# Tone_Cushion.net
KiCad netlist of a schematic drawn in Altium Designer
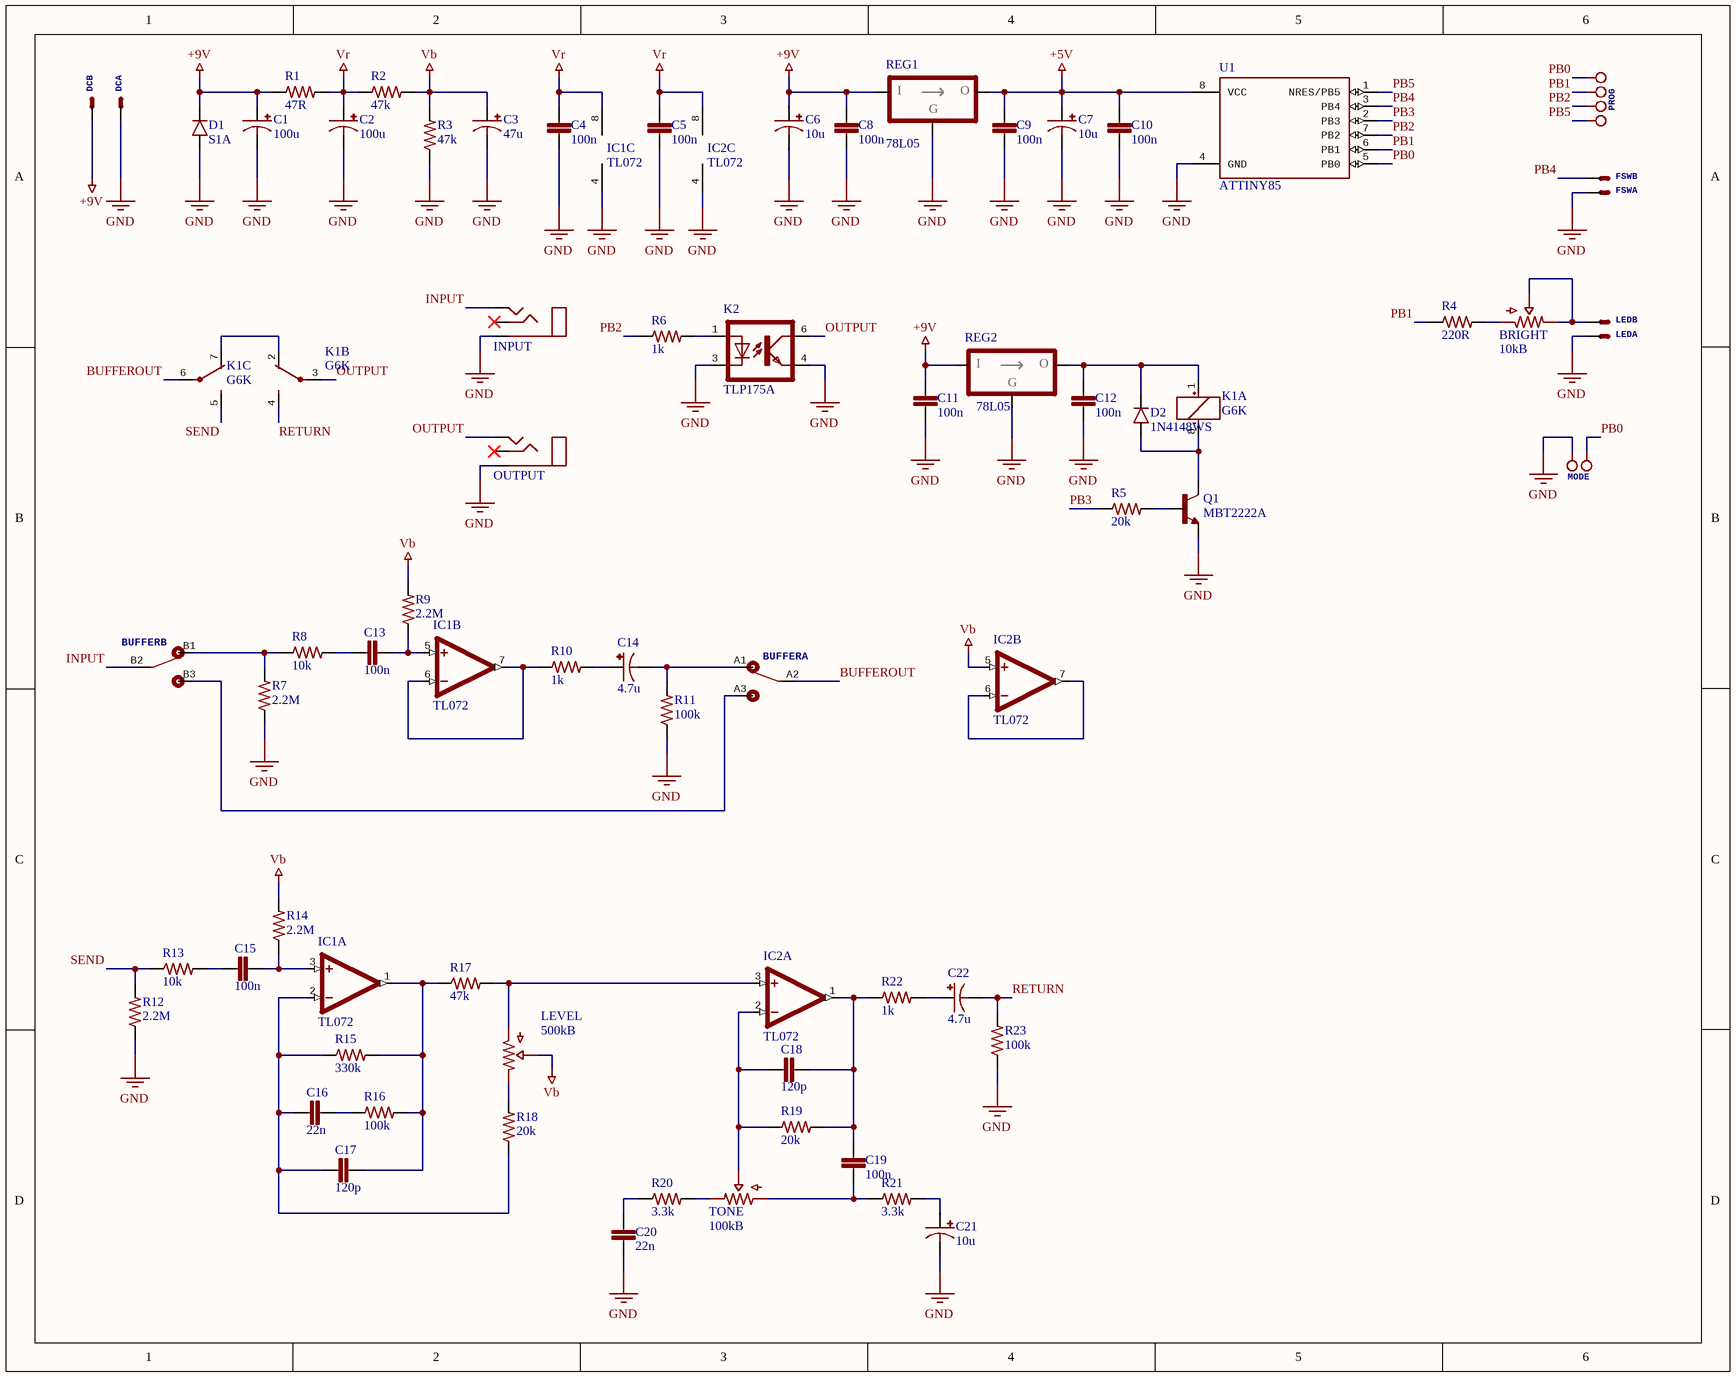
[diagram p0: Tone Cushion.SchDoc]

(export (version "E")
  (design (tool "Eeschema 10.0.6"))
  (components
    (comp (ref "BRIGHT")
      (value "10kB")
      (footprint "BOURNS_3362P")
      (description "10k Lin 3362P trimmer")
      (libsource (lib "Pedals") (part "TRIM_10kB_3362P"))
    )
    (comp (ref "BUFFER")
      (value "DPDT")
      (footprint "DPDT_SLIDE")
      (description "DPDT slide switch ON/ON")
      (libsource (lib "") (part "SW_SLIDE_DPDT_ON-ON_1"))
    )
    (comp (ref "C1")
      (value "100u")
      (footprint "CAPAE_D")
      (description "CAP ALUM 100UF 25V SMD")
      (fields
        (field (name "MANUFACTURER") "Multicomp")
        (field (name "MANUFACTURER PART NUMBER") "MCVVT025M101EA6L")
      )
      (libsource (lib "Pedals SMD") (part "MCVVT025M101EA6L"))
    )
    (comp (ref "C2")
      (value "100u")
      (footprint "CAPAE_D")
      (description "CAP ALUM 100UF 25V SMD")
      (fields
        (field (name "MANUFACTURER") "Multicomp")
        (field (name "MANUFACTURER PART NUMBER") "MCVVT025M101EA6L")
      )
      (libsource (lib "Pedals SMD") (part "MCVVT025M101EA6L"))
    )
    (comp (ref "C3")
      (value "47u")
      (footprint "CAPAE_D")
      (description "CAP ALUM 47UF 25V SMD")
      (fields
        (field (name "MANUFACTURER") "Multicomp")
        (field (name "MANUFACTURER PART NUMBER") "MCVVT025M470EA1L")
      )
      (libsource (lib "Pedals SMD") (part "MCVVT025M470EA1L"))
    )
    (comp (ref "C4")
      (value "100n")
      (footprint "CHIP_0603")
      (description "CAP CER 100NF 50V X7R 0603")
      (fields
        (field (name "MANUFACTURER") "Multicomp")
        (field (name "MANUFACTURER PART NUMBER") "MC0603B104K500CT")
      )
      (libsource (lib "Pedals SMD") (part "MC0603B104K500CT"))
    )
    (comp (ref "C5")
      (value "100n")
      (footprint "CHIP_0603")
      (description "CAP CER 100NF 50V X7R 0603")
      (fields
        (field (name "MANUFACTURER") "Multicomp")
        (field (name "MANUFACTURER PART NUMBER") "MC0603B104K500CT")
      )
      (libsource (lib "Pedals SMD") (part "MC0603B104K500CT"))
    )
    (comp (ref "C6")
      (value "10u")
      (footprint "CAPAE_B")
      (description "CAP ALUM 10UF 25V SMD")
      (fields
        (field (name "MANUFACTURER") "Multicomp")
        (field (name "MANUFACTURER PART NUMBER") "MCVVT025M100CA1L")
      )
      (libsource (lib "Pedals SMD") (part "MCVVT025M100CA1L"))
    )
    (comp (ref "C7")
      (value "10u")
      (footprint "CAPAE_B")
      (description "CAP ALUM 10UF 25V SMD")
      (fields
        (field (name "MANUFACTURER") "Multicomp")
        (field (name "MANUFACTURER PART NUMBER") "MCVVT025M100CA1L")
      )
      (libsource (lib "Pedals SMD") (part "MCVVT025M100CA1L"))
    )
    (comp (ref "C8")
      (value "100n")
      (footprint "CHIP_0603")
      (description "CAP CER 100NF 50V X7R 0603")
      (fields
        (field (name "MANUFACTURER") "Multicomp")
        (field (name "MANUFACTURER PART NUMBER") "MC0603B104K500CT")
      )
      (libsource (lib "Pedals SMD") (part "MC0603B104K500CT"))
    )
    (comp (ref "C9")
      (value "100n")
      (footprint "CHIP_0603")
      (description "CAP CER 100NF 50V X7R 0603")
      (fields
        (field (name "MANUFACTURER") "Multicomp")
        (field (name "MANUFACTURER PART NUMBER") "MC0603B104K500CT")
      )
      (libsource (lib "Pedals SMD") (part "MC0603B104K500CT"))
    )
    (comp (ref "C10")
      (value "100n")
      (footprint "CHIP_0603")
      (description "CAP CER 100NF 50V X7R 0603")
      (fields
        (field (name "MANUFACTURER") "Multicomp")
        (field (name "MANUFACTURER PART NUMBER") "MC0603B104K500CT")
      )
      (libsource (lib "Pedals SMD") (part "MC0603B104K500CT"))
    )
    (comp (ref "C11")
      (value "100n")
      (footprint "CHIP_0603")
      (description "CAP CER 100NF 50V X7R 0603")
      (fields
        (field (name "MANUFACTURER") "Multicomp")
        (field (name "MANUFACTURER PART NUMBER") "MC0603B104K500CT")
      )
      (libsource (lib "Pedals SMD") (part "MC0603B104K500CT"))
    )
    (comp (ref "C12")
      (value "100n")
      (footprint "CHIP_0603")
      (description "CAP CER 100NF 50V X7R 0603")
      (fields
        (field (name "MANUFACTURER") "Multicomp")
        (field (name "MANUFACTURER PART NUMBER") "MC0603B104K500CT")
      )
      (libsource (lib "Pedals SMD") (part "MC0603B104K500CT"))
    )
    (comp (ref "C13")
      (value "100n")
      (footprint "CHIP_1206")
      (description "CAP CER 100NF 50V C0G/NP0 1206")
      (fields
        (field (name "MANUFACTURER") "Murata")
        (field (name "MANUFACTURER PART NUMBER") "GRM31C5C1H104JA01L")
      )
      (libsource (lib "Pedals SMD") (part "GRM31C5C1H104JA01L"))
    )
    (comp (ref "C14")
      (value "4.7u")
      (footprint "CAPAE_C")
      (description "CAP ALUM 4.7UF 50V LESR SMD")
      (fields
        (field (name "MANUFACTURER") "Panasonic")
        (field (name "MANUFACTURER PART NUMBER") "EEEFC1H4R7R")
      )
      (libsource (lib "Pedals SMD") (part "EEEFC1H4R7R"))
    )
    (comp (ref "C15")
      (value "100n")
      (footprint "CHIP_1206")
      (description "CAP CER 100NF 50V C0G/NP0 1206")
      (fields
        (field (name "MANUFACTURER") "Murata")
        (field (name "MANUFACTURER PART NUMBER") "GRM31C5C1H104JA01L")
      )
      (libsource (lib "Pedals SMD") (part "GRM31C5C1H104JA01L"))
    )
    (comp (ref "C16")
      (value "22n")
      (footprint "CHIP_0805")
      (description "CAP CER 22NF 50V C0G/NP0 0805")
      (fields
        (field (name "MANUFACTURER") "Murata")
        (field (name "MANUFACTURER PART NUMBER") "GRM21B5C1H223JA01L")
      )
      (libsource (lib "") (part "GRM21B5C1H223JA01L_1"))
    )
    (comp (ref "C17")
      (value "120p")
      (footprint "CHIP_0603")
      (description "CAP CER 120PF 50V C0G/NP0 0603")
      (fields
        (field (name "MANUFACTURER") "Multicomp")
        (field (name "MANUFACTURER PART NUMBER") "MC0603N121J500CT")
      )
      (libsource (lib "Pedals SMD") (part "MC0603N121J500CT"))
    )
    (comp (ref "C18")
      (value "120p")
      (footprint "CHIP_0603")
      (description "CAP CER 120PF 50V C0G/NP0 0603")
      (fields
        (field (name "MANUFACTURER") "Multicomp")
        (field (name "MANUFACTURER PART NUMBER") "MC0603N121J500CT")
      )
      (libsource (lib "Pedals SMD") (part "MC0603N121J500CT"))
    )
    (comp (ref "C19")
      (value "100n")
      (footprint "CHIP_1206")
      (description "CAP CER 100NF 50V C0G/NP0 1206")
      (fields
        (field (name "MANUFACTURER") "Murata")
        (field (name "MANUFACTURER PART NUMBER") "GRM31C5C1H104JA01L")
      )
      (libsource (lib "") (part "GRM31C5C1H104JA01L_1"))
    )
    (comp (ref "C20")
      (value "22n")
      (footprint "CHIP_0805")
      (description "CAP CER 22NF 50V C0G/NP0 0805")
      (fields
        (field (name "MANUFACTURER") "Murata")
        (field (name "MANUFACTURER PART NUMBER") "GRM21B5C1H223JA01L")
      )
      (libsource (lib "Pedals SMD") (part "GRM21B5C1H223JA01L"))
    )
    (comp (ref "C21")
      (value "10u")
      (footprint "CAPAE_C")
      (description "CAP ALUM 10UF 20% 50V LESR SMD")
      (fields
        (field (name "MANUFACTURER") "Panasonic")
        (field (name "MANUFACTURER PART NUMBER") "EEEFC1H100P")
      )
      (libsource (lib "Pedals SMD") (part "EEEFC1H100P"))
    )
    (comp (ref "C22")
      (value "4.7u")
      (footprint "CAPAE_C")
      (description "CAP ALUM 4.7UF 50V LESR SMD")
      (fields
        (field (name "MANUFACTURER") "Panasonic")
        (field (name "MANUFACTURER PART NUMBER") "EEEFC1H4R7R")
      )
      (libsource (lib "Pedals SMD") (part "EEEFC1H4R7R"))
    )
    (comp (ref "D1")
      (value "S1A")
      (footprint "DO214")
      (description "DIODE GEN PURP 50V 1A SMA")
      (fields (field (name "MANUFACTURER") "ON Semiconductor / Fairchild"))
      (libsource (lib "Pedals SMD") (part "S1A"))
    )
    (comp (ref "D2")
      (value "1N4148WS")
      (footprint "SOD323")
      (description "DIODE GEN PURP 75V 150MA SOD323F")
      (fields (field (name "MANUFACTURER") "ON Semiconductor / Fairchild"))
      (libsource (lib "Pedals SMD") (part "1N4148WS"))
    )
    (comp (ref "DC")
      (value "J_JST-XH-02")
      (footprint "JST-XH-02")
      (description "2 Pins male XH header")
      (libsource (lib "Pedals") (part "J_JST-XH-02"))
    )
    (comp (ref "FSW")
      (value "J_JST-XH-02")
      (footprint "JST-XH-02")
      (description "2 Pins male XH header")
      (libsource (lib "Pedals") (part "J_JST-XH-02"))
    )
    (comp (ref "IC1")
      (value "TL072")
      (footprint "SO-8")
      (description "IC OPAMP JFET 4MHZ 8SO")
      (fields
        (field (name "MANUFACTURER") "STMicroelectronics")
        (field (name "MANUFACTURER PART NUMBER") "TL072CDT")
      )
      (libsource (lib "Pedals SMD") (part "TL072CDT"))
    )
    (comp (ref "IC2")
      (value "TL072")
      (footprint "SO-8")
      (description "IC OPAMP JFET 4MHZ 8SO")
      (fields
        (field (name "MANUFACTURER") "STMicroelectronics")
        (field (name "MANUFACTURER PART NUMBER") "TL072CDT")
      )
      (libsource (lib "Pedals SMD") (part "TL072CDT"))
    )
    (comp (ref "INPUT")
      (value "J_STEREO")
      (footprint "STEREO")
      (description "6.35mm stereo insulated socket jack PCB mounted")
      (libsource (lib "Pedals") (part "J_STEREO"))
    )
    (comp (ref "K1")
      (value "G6K")
      (footprint "G6K")
      (description "OMRON - G6K-2F 5DC - RELAY, SIGNAL, DPDT, 30VDC, 1A")
      (fields (field (name "MANUFACTURER") "Cliff") (field (name "MANUFACTURER PART NUMBER") "G6K-2F5DC"))
      (libsource (lib "") (part "G6K-2F5DC_2"))
    )
    (comp (ref "K2")
      (value "TLP175A")
      (footprint "TLP175A")
      (description "Toshiba TLP175A AC Input MOSFET Output Optocoupler, Surface Mount, 4-Pin SOIC")
      (fields (field (name "MANUFACTURER") "Toshiba"))
      (libsource (lib "Pedals SMD") (part "TLP175A"))
    )
    (comp (ref "LED")
      (value "J_JST-XH-02")
      (footprint "JST-XH-02")
      (description "2 Pins male XH header")
      (libsource (lib "Pedals") (part "J_JST-XH-02"))
    )
    (comp (ref "LEVEL")
      (value "500kB")
      (footprint "ALPHA_16mm_BOTTOM")
      (description "500k Lin potentiometer round shaft")
      (libsource (lib "Pedals") (part "POT_500kB_ALPHA_16mm"))
    )
    (comp (ref "MODE")
      (value "J_HEADER_2PINS")
      (footprint "HEADER_2PINS")
      (description "2 Pins male header")
      (libsource (lib "Pedals") (part "J_HEADER_2PINS"))
    )
    (comp (ref "OUTPUT")
      (value "J_STEREO")
      (footprint "STEREO")
      (description "6.35mm stereo insulated socket jack PCB mounted")
      (libsource (lib "Pedals") (part "J_STEREO"))
    )
    (comp (ref "PROG")
      (value "J_HEADER_4PINS_FEM")
      (footprint "HEADER_4Pins_FEM")
      (description "4 Pins female header")
      (libsource (lib "Pedals") (part "J_HEADER_4PINS_FEM"))
    )
    (comp (ref "Q1")
      (value "MBT2222A")
      (footprint "SOT323")
      (description "TRANS NPN 40V 0.6A SOT323")
      (fields
        (field (name "MANUFACTURER") "ON Semiconductor")
        (field (name "MANUFACTURER PART NUMBER") "MMBT2222AWT1G")
      )
      (libsource (lib "Pedals SMD") (part "MMBT2222AWT1G"))
    )
    (comp (ref "R1")
      (value "47R")
      (footprint "CHIP_R_1206")
      (description "RES SMD 47 OHM 1% 1/4W 1206")
      (fields
        (field (name "MANUFACTURER") "Vishay")
        (field (name "MANUFACTURER PART NUMBER") "CRCW120647R0FKEA")
      )
      (libsource (lib "Pedals SMD") (part "CRCW120647R0FKEA"))
    )
    (comp (ref "R2")
      (value "47k")
      (footprint "CHIP_R_1206")
      (description "RES SMD 47K OHM 1% 1/4W 1206")
      (fields
        (field (name "MANUFACTURER") "Vishay")
        (field (name "MANUFACTURER PART NUMBER") "CRCW120647K0FKEA")
      )
      (libsource (lib "Pedals SMD") (part "CRCW120647K0FKEA"))
    )
    (comp (ref "R3")
      (value "47k")
      (footprint "CHIP_R_1206")
      (description "RES SMD 47K OHM 1% 1/4W 1206")
      (fields
        (field (name "MANUFACTURER") "Vishay")
        (field (name "MANUFACTURER PART NUMBER") "CRCW120647K0FKEA")
      )
      (libsource (lib "Pedals SMD") (part "CRCW120647K0FKEA"))
    )
    (comp (ref "R4")
      (value "220R")
      (footprint "CHIP_R_1206")
      (description "RES SMD 220 OHM 1% 1/4W 1206")
      (fields
        (field (name "MANUFACTURER") "Vishay")
        (field (name "MANUFACTURER PART NUMBER") "CRCW1206220RFKEA")
      )
      (libsource (lib "Pedals SMD") (part "CRCW1206220RFKEA"))
    )
    (comp (ref "R5")
      (value "20k")
      (footprint "CHIP_R_0603")
      (description "RES SMD 20K OHM 1% 1/10W 0603")
      (fields
        (field (name "MANUFACTURER") "Vishay")
        (field (name "MANUFACTURER PART NUMBER") "CRCW060320K0FKEA")
      )
      (libsource (lib "Pedals SMD") (part "CRCW060320K0FKEA"))
    )
    (comp (ref "R6")
      (value "1k")
      (footprint "CHIP_R_0603")
      (description "RES SMD 1K OHM 1% 1/10W 0603")
      (fields
        (field (name "MANUFACTURER") "Vishay Dale")
        (field (name "MANUFACTURER PART NUMBER") "CRCW06031K00FKEA")
      )
      (libsource (lib "Pedals SMD") (part "CRCW06031K00FKEA"))
    )
    (comp (ref "R7")
      (value "2.2M")
      (footprint "CHIP_R_0603")
      (description "RES SMD 2.2M OHM 1% 1/10W 0603")
      (fields
        (field (name "MANUFACTURER") "Vishay")
        (field (name "MANUFACTURER PART NUMBER") "CRCW06032M20FKEA")
      )
      (libsource (lib "Pedals SMD") (part "CRCW06032M20FKEA"))
    )
    (comp (ref "R8")
      (value "10k")
      (footprint "CHIP_R_0603")
      (description "RES SMD 10K OHM 1% 1/10W 0603")
      (fields
        (field (name "MANUFACTURER") "Vishay")
        (field (name "MANUFACTURER PART NUMBER") "CRCW060310K0FKEA")
      )
      (libsource (lib "Pedals SMD") (part "CRCW060310K0FKEA"))
    )
    (comp (ref "R9")
      (value "2.2M")
      (footprint "CHIP_R_0603")
      (description "RES SMD 2.2M OHM 1% 1/10W 0603")
      (fields
        (field (name "MANUFACTURER") "Vishay")
        (field (name "MANUFACTURER PART NUMBER") "CRCW06032M20FKEA")
      )
      (libsource (lib "Pedals SMD") (part "CRCW06032M20FKEA"))
    )
    (comp (ref "R10")
      (value "1k")
      (footprint "CHIP_R_0603")
      (description "RES SMD 1K OHM 1% 1/10W 0603")
      (fields
        (field (name "MANUFACTURER") "Vishay Dale")
        (field (name "MANUFACTURER PART NUMBER") "CRCW06031K00FKEA")
      )
      (libsource (lib "Pedals SMD") (part "CRCW06031K00FKEA"))
    )
    (comp (ref "R11")
      (value "100k")
      (footprint "CHIP_R_0603")
      (description "RES SMD 100K OHM 1% 1/10W 0603")
      (fields
        (field (name "MANUFACTURER") "Vishay")
        (field (name "MANUFACTURER PART NUMBER") "CRCW0603100KFKEA")
      )
      (libsource (lib "Pedals SMD") (part "CRCW0603100KFKEA"))
    )
    (comp (ref "R12")
      (value "2.2M")
      (footprint "CHIP_R_0603")
      (description "RES SMD 2.2M OHM 1% 1/10W 0603")
      (fields
        (field (name "MANUFACTURER") "Vishay")
        (field (name "MANUFACTURER PART NUMBER") "CRCW06032M20FKEA")
      )
      (libsource (lib "Pedals SMD") (part "CRCW06032M20FKEA"))
    )
    (comp (ref "R13")
      (value "10k")
      (footprint "CHIP_R_0603")
      (description "RES SMD 10K OHM 1% 1/10W 0603")
      (fields
        (field (name "MANUFACTURER") "Vishay")
        (field (name "MANUFACTURER PART NUMBER") "CRCW060310K0FKEA")
      )
      (libsource (lib "Pedals SMD") (part "CRCW060310K0FKEA"))
    )
    (comp (ref "R14")
      (value "2.2M")
      (footprint "CHIP_R_0603")
      (description "RES SMD 2.2M OHM 1% 1/10W 0603")
      (fields
        (field (name "MANUFACTURER") "Vishay")
        (field (name "MANUFACTURER PART NUMBER") "CRCW06032M20FKEA")
      )
      (libsource (lib "Pedals SMD") (part "CRCW06032M20FKEA"))
    )
    (comp (ref "R15")
      (value "330k")
      (footprint "CHIP_R_0603")
      (description "RES SMD 330K OHM 1% 1/10W 0603")
      (fields
        (field (name "MANUFACTURER") "Vishay")
        (field (name "MANUFACTURER PART NUMBER") "CRCW0603330KFKEA")
      )
      (libsource (lib "Pedals SMD") (part "CRCW0603330KFKEA"))
    )
    (comp (ref "R16")
      (value "100k")
      (footprint "CHIP_R_0603")
      (description "RES SMD 100K OHM 1% 1/10W 0603")
      (fields
        (field (name "MANUFACTURER") "Vishay")
        (field (name "MANUFACTURER PART NUMBER") "CRCW0603100KFKEA")
      )
      (libsource (lib "Pedals SMD") (part "CRCW0603100KFKEA"))
    )
    (comp (ref "R17")
      (value "47k")
      (footprint "CHIP_R_0603")
      (description "RES SMD 47K OHM 1% 1/10W 0603")
      (fields
        (field (name "MANUFACTURER") "Vishay")
        (field (name "MANUFACTURER PART NUMBER") "CRCW060347K0FKEA")
      )
      (libsource (lib "Pedals SMD") (part "CRCW060347K0FKEA"))
    )
    (comp (ref "R18")
      (value "20k")
      (footprint "CHIP_R_0603")
      (description "RES SMD 20K OHM 1% 1/10W 0603")
      (fields
        (field (name "MANUFACTURER") "Vishay")
        (field (name "MANUFACTURER PART NUMBER") "CRCW060320K0FKEA")
      )
      (libsource (lib "Pedals SMD") (part "CRCW060320K0FKEA"))
    )
    (comp (ref "R19")
      (value "20k")
      (footprint "CHIP_R_0603")
      (description "RES SMD 20K OHM 1% 1/10W 0603")
      (fields
        (field (name "MANUFACTURER") "Vishay")
        (field (name "MANUFACTURER PART NUMBER") "CRCW060320K0FKEA")
      )
      (libsource (lib "Pedals SMD") (part "CRCW060320K0FKEA"))
    )
    (comp (ref "R20")
      (value "3.3k")
      (footprint "CHIP_R_0603")
      (description "RES SMD 3.3K OHM 1% 1/10W 0603")
      (fields
        (field (name "MANUFACTURER") "Vishay")
        (field (name "MANUFACTURER PART NUMBER") "CRCW06033K30FKEA")
      )
      (libsource (lib "Pedals SMD") (part "CRCW06033K30FKEA"))
    )
    (comp (ref "R21")
      (value "3.3k")
      (footprint "CHIP_R_0603")
      (description "RES SMD 3.3K OHM 1% 1/10W 0603")
      (fields
        (field (name "MANUFACTURER") "Vishay")
        (field (name "MANUFACTURER PART NUMBER") "CRCW06033K30FKEA")
      )
      (libsource (lib "Pedals SMD") (part "CRCW06033K30FKEA"))
    )
    (comp (ref "R22")
      (value "1k")
      (footprint "CHIP_R_0603")
      (description "RES SMD 1K OHM 1% 1/10W 0603")
      (fields
        (field (name "MANUFACTURER") "Vishay Dale")
        (field (name "MANUFACTURER PART NUMBER") "CRCW06031K00FKEA")
      )
      (libsource (lib "Pedals SMD") (part "CRCW06031K00FKEA"))
    )
    (comp (ref "R23")
      (value "100k")
      (footprint "CHIP_R_0603")
      (description "RES SMD 100K OHM 1% 1/10W 0603")
      (fields
        (field (name "MANUFACTURER") "Vishay")
        (field (name "MANUFACTURER PART NUMBER") "CRCW0603100KFKEA")
      )
      (libsource (lib "Pedals SMD") (part "CRCW0603100KFKEA"))
    )
    (comp (ref "REG1")
      (value "78L05")
      (footprint "SOT23-3")
      (description "TAIWAN SEMICONDUCTOR - TS78L05CX RFG - REG 3-TERMINAL 100MA, SMD, SOT23-3")
      (fields
        (field (name "MANUFACTURER") "Taiwan Semiconductor")
        (field (name "MANUFACTURER PART NUMBER") "TS78L05CXRFG")
      )
      (libsource (lib "Pedals SMD") (part "TS78L05CXRFG"))
    )
    (comp (ref "REG2")
      (value "78L05")
      (footprint "SOT23-3")
      (description "TAIWAN SEMICONDUCTOR - TS78L05CX RFG - REG 3-TERMINAL 100MA, SMD, SOT23-3")
      (fields
        (field (name "MANUFACTURER") "Taiwan Semiconductor")
        (field (name "MANUFACTURER PART NUMBER") "TS78L05CXRFG")
      )
      (libsource (lib "Pedals SMD") (part "TS78L05CXRFG"))
    )
    (comp (ref "TONE")
      (value "100kB")
      (footprint "ALPHA_16mm_BOTTOM")
      (description "100k Lin potentiometer round shaft")
      (libsource (lib "Pedals") (part "POT_100kB_ALPHA_16mm"))
    )
    (comp (ref "U1")
      (value "ATTINY85")
      (footprint "SOP8")
      (description "IC, 8BIT MCU, AVR TINY, 20MHZ, 8-SOIC")
      (fields
        (field (name "MANUFACTURER") "Microchip / Atmel")
        (field (name "MANUFACTURER PART NUMBER") "ATTINY85-20SU")
      )
      (libsource (lib "Pedals SMD") (part "ATTINY85-20SU"))
    )
  )
  (nets
    (net (code "1") (name "+5V") (class "Default")
      (node (ref "C10") (pin "1") (pinfunction "1_1") (pintype "passive"))
      (node (ref "C7") (pin "+") (pinfunction "+_+") (pintype "passive"))
      (node (ref "C9") (pin "1") (pinfunction "1_1") (pintype "passive"))
      (node (ref "REG1") (pin "1") (pinfunction "OUTPUT_1") (pintype "power_in"))
      (node (ref "U1") (pin "8") (pinfunction "VCC_8") (pintype "power_in"))
    )
    (net (code "2") (name "+9V") (class "Default")
      (node (ref "C1") (pin "+") (pinfunction "+_+") (pintype "passive"))
      (node (ref "C11") (pin "1") (pinfunction "1_1") (pintype "passive"))
      (node (ref "C6") (pin "+") (pinfunction "+_+") (pintype "passive"))
      (node (ref "C8") (pin "1") (pinfunction "1_1") (pintype "passive"))
      (node (ref "D1") (pin "1") (pinfunction "1_1") (pintype "passive"))
      (node (ref "DC") (pin "1") (pinfunction "S_1") (pintype "passive"))
      (node (ref "R1") (pin "1") (pinfunction "1_1") (pintype "passive"))
      (node (ref "REG1") (pin "2") (pinfunction "INPUT_2") (pintype "power_in"))
      (node (ref "REG2") (pin "2") (pinfunction "INPUT_2") (pintype "power_in"))
    )
    (net (code "3") (name "/BUFFEROUT") (class "Default")
      (node (ref "BUFFER") (pin "A2") (pinfunction "2_A2") (pintype "passive"))
      (node (ref "K1") (pin "6") (pinfunction "P_6") (pintype "passive"))
    )
    (net (code "4") (name "/INPUT") (class "Default")
      (node (ref "BUFFER") (pin "B2") (pinfunction "2_B2") (pintype "passive"))
      (node (ref "INPUT") (pin "T") (pinfunction "T_T") (pintype "passive"))
    )
    (net (code "5") (name "/OUTPUT") (class "Default")
      (node (ref "K1") (pin "3") (pinfunction "P_3") (pintype "passive"))
      (node (ref "K2") (pin "6") (pinfunction "COL_6") (pintype "passive"))
      (node (ref "OUTPUT") (pin "T") (pinfunction "T_T") (pintype "passive"))
    )
    (net (code "6") (name "/PB0") (class "Default")
      (node (ref "MODE") (pin "2") (pinfunction "2_2") (pintype "passive"))
      (node (ref "PROG") (pin "4") (pinfunction "4_4") (pintype "passive"))
      (node (ref "U1") (pin "5") (pinfunction "PB0_5") (pintype "bidirectional"))
    )
    (net (code "7") (name "/PB1") (class "Default")
      (node (ref "PROG") (pin "3") (pinfunction "3_3") (pintype "passive"))
      (node (ref "R4") (pin "1") (pinfunction "1_1") (pintype "passive"))
      (node (ref "U1") (pin "6") (pinfunction "PB1_6") (pintype "bidirectional"))
    )
    (net (code "8") (name "/PB2") (class "Default")
      (node (ref "PROG") (pin "2") (pinfunction "2_2") (pintype "passive"))
      (node (ref "R6") (pin "1") (pinfunction "1_1") (pintype "passive"))
      (node (ref "U1") (pin "7") (pinfunction "PB2_7") (pintype "bidirectional"))
    )
    (net (code "9") (name "/PB3") (class "Default")
      (node (ref "R5") (pin "1") (pinfunction "1_1") (pintype "passive"))
      (node (ref "U1") (pin "2") (pinfunction "PB3_2") (pintype "bidirectional"))
    )
    (net (code "10") (name "/PB4") (class "Default")
      (node (ref "FSW") (pin "1") (pinfunction "S_1") (pintype "passive"))
      (node (ref "U1") (pin "3") (pinfunction "PB4_3") (pintype "bidirectional"))
    )
    (net (code "11") (name "/PB5") (class "Default")
      (node (ref "PROG") (pin "1") (pinfunction "1_1") (pintype "passive"))
      (node (ref "U1") (pin "1") (pinfunction "NRES/PB5_1") (pintype "bidirectional"))
    )
    (net (code "12") (name "/RETURN") (class "Default")
      (node (ref "C22") (pin "-") (pinfunction "-_-") (pintype "passive"))
      (node (ref "K1") (pin "4") (pinfunction "S_4") (pintype "passive"))
      (node (ref "R23") (pin "2") (pinfunction "2_2") (pintype "passive"))
    )
    (net (code "13") (name "/SEND") (class "Default")
      (node (ref "K1") (pin "5") (pinfunction "S_5") (pintype "passive"))
      (node (ref "R12") (pin "2") (pinfunction "2_2") (pintype "passive"))
      (node (ref "R13") (pin "1") (pinfunction "1_1") (pintype "passive"))
    )
    (net (code "14") (name "GND") (class "Default")
      (node (ref "C1") (pin "-") (pinfunction "-_-") (pintype "passive"))
      (node (ref "C10") (pin "2") (pinfunction "2_2") (pintype "passive"))
      (node (ref "C11") (pin "2") (pinfunction "2_2") (pintype "passive"))
      (node (ref "C12") (pin "2") (pinfunction "2_2") (pintype "passive"))
      (node (ref "C2") (pin "-") (pinfunction "-_-") (pintype "passive"))
      (node (ref "C20") (pin "2") (pinfunction "2_2") (pintype "passive"))
      (node (ref "C21") (pin "-") (pinfunction "-_-") (pintype "passive"))
      (node (ref "C3") (pin "-") (pinfunction "-_-") (pintype "passive"))
      (node (ref "C4") (pin "2") (pinfunction "2_2") (pintype "passive"))
      (node (ref "C5") (pin "2") (pinfunction "2_2") (pintype "passive"))
      (node (ref "C6") (pin "-") (pinfunction "-_-") (pintype "passive"))
      (node (ref "C7") (pin "-") (pinfunction "-_-") (pintype "passive"))
      (node (ref "C8") (pin "2") (pinfunction "2_2") (pintype "passive"))
      (node (ref "C9") (pin "2") (pinfunction "2_2") (pintype "passive"))
      (node (ref "D1") (pin "2") (pinfunction "2_2") (pintype "passive"))
      (node (ref "DC") (pin "2") (pinfunction "S_2") (pintype "passive"))
      (node (ref "FSW") (pin "2") (pinfunction "S_2") (pintype "passive"))
      (node (ref "IC1") (pin "4") (pinfunction "V-_4") (pintype "power_in"))
      (node (ref "IC2") (pin "4") (pinfunction "V-_4") (pintype "power_in"))
      (node (ref "INPUT") (pin "S") (pinfunction "S_S") (pintype "passive"))
      (node (ref "K2") (pin "3") (pinfunction "C_3") (pintype "passive"))
      (node (ref "K2") (pin "4") (pinfunction "EMIT_4") (pintype "passive"))
      (node (ref "LED") (pin "2") (pinfunction "S_2") (pintype "passive"))
      (node (ref "MODE") (pin "1") (pinfunction "1_1") (pintype "passive"))
      (node (ref "OUTPUT") (pin "S") (pinfunction "S_S") (pintype "passive"))
      (node (ref "Q1") (pin "2") (pinfunction "E_2") (pintype "passive"))
      (node (ref "R11") (pin "1") (pinfunction "1_1") (pintype "passive"))
      (node (ref "R12") (pin "1") (pinfunction "1_1") (pintype "passive"))
      (node (ref "R23") (pin "1") (pinfunction "1_1") (pintype "passive"))
      (node (ref "R3") (pin "1") (pinfunction "1_1") (pintype "passive"))
      (node (ref "R7") (pin "1") (pinfunction "1_1") (pintype "passive"))
      (node (ref "REG1") (pin "3") (pinfunction "COMMON_3") (pintype "power_in"))
      (node (ref "REG2") (pin "3") (pinfunction "COMMON_3") (pintype "power_in"))
      (node (ref "U1") (pin "4") (pinfunction "GND_4") (pintype "power_in"))
    )
    (net (code "15") (name "Net-(BRIGHT-Pad1)") (class "Default")
      (node (ref "BRIGHT") (pin "1") (pinfunction "1_1") (pintype "passive"))
      (node (ref "R4") (pin "2") (pinfunction "2_2") (pintype "passive"))
    )
    (net (code "16") (name "Net-(BUFFERA-1)") (class "Default")
      (node (ref "BUFFER") (pin "A1") (pinfunction "1_A1") (pintype "passive"))
      (node (ref "C14") (pin "-") (pinfunction "-_-") (pintype "passive"))
      (node (ref "R11") (pin "2") (pinfunction "2_2") (pintype "passive"))
    )
    (net (code "17") (name "Net-(BUFFERA-3)") (class "Default")
      (node (ref "BUFFER") (pin "A3") (pinfunction "3_A3") (pintype "passive"))
      (node (ref "BUFFER") (pin "B3") (pinfunction "3_B3") (pintype "passive"))
    )
    (net (code "18") (name "Net-(BUFFERB-1)") (class "Default")
      (node (ref "BUFFER") (pin "B1") (pinfunction "1_B1") (pintype "passive"))
      (node (ref "R7") (pin "2") (pinfunction "2_2") (pintype "passive"))
      (node (ref "R8") (pin "1") (pinfunction "1_1") (pintype "passive"))
    )
    (net (code "19") (name "Net-(C13-Pad2)") (class "Default")
      (node (ref "C13") (pin "2") (pinfunction "2_2") (pintype "passive"))
      (node (ref "R8") (pin "2") (pinfunction "2_2") (pintype "passive"))
    )
    (net (code "20") (name "Net-(C14-Pad+)") (class "Default")
      (node (ref "C14") (pin "+") (pinfunction "+_+") (pintype "passive"))
      (node (ref "R10") (pin "2") (pinfunction "2_2") (pintype "passive"))
    )
    (net (code "21") (name "Net-(C15-Pad2)") (class "Default")
      (node (ref "C15") (pin "2") (pinfunction "2_2") (pintype "passive"))
      (node (ref "R13") (pin "2") (pinfunction "2_2") (pintype "passive"))
    )
    (net (code "22") (name "Net-(C16-Pad1)") (class "Default")
      (node (ref "C16") (pin "1") (pinfunction "1_1") (pintype "passive"))
      (node (ref "R16") (pin "1") (pinfunction "1_1") (pintype "passive"))
    )
    (net (code "23") (name "Net-(C19-Pad2)") (class "Default")
      (node (ref "C19") (pin "2") (pinfunction "2_2") (pintype "passive"))
      (node (ref "R21") (pin "1") (pinfunction "1_1") (pintype "passive"))
      (node (ref "TONE") (pin "1") (pinfunction "1_1") (pintype "passive"))
    )
    (net (code "24") (name "Net-(C20-Pad1)") (class "Default")
      (node (ref "C20") (pin "1") (pinfunction "1_1") (pintype "passive"))
      (node (ref "R20") (pin "1") (pinfunction "1_1") (pintype "passive"))
    )
    (net (code "25") (name "Net-(C21-Pad+)") (class "Default")
      (node (ref "C21") (pin "+") (pinfunction "+_+") (pintype "passive"))
      (node (ref "R21") (pin "2") (pinfunction "2_2") (pintype "passive"))
    )
    (net (code "26") (name "Net-(C22-Pad+)") (class "Default")
      (node (ref "C22") (pin "+") (pinfunction "+_+") (pintype "passive"))
      (node (ref "R22") (pin "2") (pinfunction "2_2") (pintype "passive"))
    )
    (net (code "27") (name "Net-(IC1A-+IN)") (class "Default")
      (node (ref "C15") (pin "1") (pinfunction "1_1") (pintype "passive"))
      (node (ref "IC1") (pin "3") (pinfunction "+IN_3") (pintype "input"))
      (node (ref "R14") (pin "1") (pinfunction "1_1") (pintype "passive"))
    )
    (net (code "28") (name "Net-(IC1A--IN)") (class "Default")
      (node (ref "C16") (pin "2") (pinfunction "2_2") (pintype "passive"))
      (node (ref "C17") (pin "2") (pinfunction "2_2") (pintype "passive"))
      (node (ref "IC1") (pin "2") (pinfunction "-IN_2") (pintype "input"))
      (node (ref "R15") (pin "1") (pinfunction "1_1") (pintype "passive"))
      (node (ref "R18") (pin "1") (pinfunction "1_1") (pintype "passive"))
    )
    (net (code "29") (name "Net-(IC1A-OUT)") (class "Default")
      (node (ref "C17") (pin "1") (pinfunction "1_1") (pintype "passive"))
      (node (ref "IC1") (pin "1") (pinfunction "OUT_1") (pintype "output"))
      (node (ref "R15") (pin "2") (pinfunction "2_2") (pintype "passive"))
      (node (ref "R16") (pin "2") (pinfunction "2_2") (pintype "passive"))
      (node (ref "R17") (pin "1") (pinfunction "1_1") (pintype "passive"))
    )
    (net (code "30") (name "Net-(IC1B-+IN)") (class "Default")
      (node (ref "C13") (pin "1") (pinfunction "1_1") (pintype "passive"))
      (node (ref "IC1") (pin "5") (pinfunction "+IN_5") (pintype "input"))
      (node (ref "R9") (pin "1") (pinfunction "1_1") (pintype "passive"))
    )
    (net (code "31") (name "Net-(IC1B--IN)") (class "Default")
      (node (ref "IC1") (pin "6") (pinfunction "-IN_6") (pintype "input"))
      (node (ref "IC1") (pin "7") (pinfunction "OUT_7") (pintype "output"))
      (node (ref "R10") (pin "1") (pinfunction "1_1") (pintype "passive"))
    )
    (net (code "32") (name "Net-(IC2A-+IN)") (class "Default")
      (node (ref "IC2") (pin "3") (pinfunction "+IN_3") (pintype "input"))
      (node (ref "LEVEL") (pin "1") (pinfunction "1_1") (pintype "passive"))
      (node (ref "R17") (pin "2") (pinfunction "2_2") (pintype "passive"))
    )
    (net (code "33") (name "Net-(IC2A--IN)") (class "Default")
      (node (ref "C18") (pin "2") (pinfunction "2_2") (pintype "passive"))
      (node (ref "IC2") (pin "2") (pinfunction "-IN_2") (pintype "input"))
      (node (ref "R19") (pin "1") (pinfunction "1_1") (pintype "passive"))
      (node (ref "TONE") (pin "2") (pinfunction "2_2") (pintype "passive"))
    )
    (net (code "34") (name "Net-(IC2A-OUT)") (class "Default")
      (node (ref "C18") (pin "1") (pinfunction "1_1") (pintype "passive"))
      (node (ref "C19") (pin "1") (pinfunction "1_1") (pintype "passive"))
      (node (ref "IC2") (pin "1") (pinfunction "OUT_1") (pintype "output"))
      (node (ref "R19") (pin "2") (pinfunction "2_2") (pintype "passive"))
      (node (ref "R22") (pin "1") (pinfunction "1_1") (pintype "passive"))
    )
    (net (code "35") (name "Net-(IC2B--IN)") (class "Default")
      (node (ref "IC2") (pin "6") (pinfunction "-IN_6") (pintype "input"))
      (node (ref "IC2") (pin "7") (pinfunction "OUT_7") (pintype "output"))
    )
    (net (code "36") (name "Net-(K1A-+)") (class "Default")
      (node (ref "C12") (pin "1") (pinfunction "1_1") (pintype "passive"))
      (node (ref "D2") (pin "1") (pinfunction "1_1") (pintype "passive"))
      (node (ref "K1") (pin "1") (pinfunction "+_1") (pintype "passive"))
      (node (ref "REG2") (pin "1") (pinfunction "OUTPUT_1") (pintype "power_in"))
    )
    (net (code "37") (name "Net-(K1A--)") (class "Default")
      (node (ref "D2") (pin "2") (pinfunction "2_2") (pintype "passive"))
      (node (ref "K1") (pin "8") (pinfunction "-_8") (pintype "passive"))
      (node (ref "Q1") (pin "3") (pinfunction "C_3") (pintype "passive"))
    )
    (net (code "38") (name "Net-(K1B-O)") (class "Default")
      (node (ref "K1") (pin "2") (pinfunction "O_2") (pintype "passive"))
      (node (ref "K1") (pin "7") (pinfunction "O_7") (pintype "passive"))
    )
    (net (code "39") (name "Net-(K2-A)") (class "Default")
      (node (ref "K2") (pin "1") (pinfunction "A_1") (pintype "passive"))
      (node (ref "R6") (pin "2") (pinfunction "2_2") (pintype "passive"))
    )
    (net (code "40") (name "Net-(LEDB-S)") (class "Default")
      (node (ref "BRIGHT") (pin "2") (pinfunction "2_2") (pintype "passive"))
      (node (ref "BRIGHT") (pin "3") (pinfunction "3_3") (pintype "passive"))
      (node (ref "LED") (pin "1") (pinfunction "S_1") (pintype "passive"))
    )
    (net (code "41") (name "Net-(LEVEL-Pad3)") (class "Default")
      (node (ref "LEVEL") (pin "3") (pinfunction "3_3") (pintype "passive"))
      (node (ref "R18") (pin "2") (pinfunction "2_2") (pintype "passive"))
    )
    (net (code "42") (name "Net-(Q1-B)") (class "Default")
      (node (ref "Q1") (pin "1") (pinfunction "B_1") (pintype "passive"))
      (node (ref "R5") (pin "2") (pinfunction "2_2") (pintype "passive"))
    )
    (net (code "43") (name "Net-(R20-Pad2)") (class "Default")
      (node (ref "R20") (pin "2") (pinfunction "2_2") (pintype "passive"))
      (node (ref "TONE") (pin "3") (pinfunction "3_3") (pintype "passive"))
    )
    (net (code "44") (name "Vb") (class "Default")
      (node (ref "C3") (pin "+") (pinfunction "+_+") (pintype "passive"))
      (node (ref "IC2") (pin "5") (pinfunction "+IN_5") (pintype "input"))
      (node (ref "LEVEL") (pin "2") (pinfunction "2_2") (pintype "passive"))
      (node (ref "R14") (pin "2") (pinfunction "2_2") (pintype "passive"))
      (node (ref "R2") (pin "2") (pinfunction "2_2") (pintype "passive"))
      (node (ref "R3") (pin "2") (pinfunction "2_2") (pintype "passive"))
      (node (ref "R9") (pin "2") (pinfunction "2_2") (pintype "passive"))
    )
    (net (code "45") (name "Vr") (class "Default")
      (node (ref "C2") (pin "+") (pinfunction "+_+") (pintype "passive"))
      (node (ref "C4") (pin "1") (pinfunction "1_1") (pintype "passive"))
      (node (ref "C5") (pin "1") (pinfunction "1_1") (pintype "passive"))
      (node (ref "IC1") (pin "8") (pinfunction "V+_8") (pintype "power_in"))
      (node (ref "IC2") (pin "8") (pinfunction "V+_8") (pintype "power_in"))
      (node (ref "R1") (pin "2") (pinfunction "2_2") (pintype "passive"))
      (node (ref "R2") (pin "1") (pinfunction "1_1") (pintype "passive"))
    )
    (net (code "46") (name "unconnected-(INPUT-PadR)") (class "Default")
      (node (ref "INPUT") (pin "R") (pinfunction "R_R") (pintype "passive+no_connect"))
    )
    (net (code "47") (name "unconnected-(OUTPUT-PadR)") (class "Default")
      (node (ref "OUTPUT") (pin "R") (pinfunction "R_R") (pintype "passive+no_connect"))
    )
  )
)
